# isoSPI_Interface.net
KiCad netlist of a schematic drawn in Altium Designer
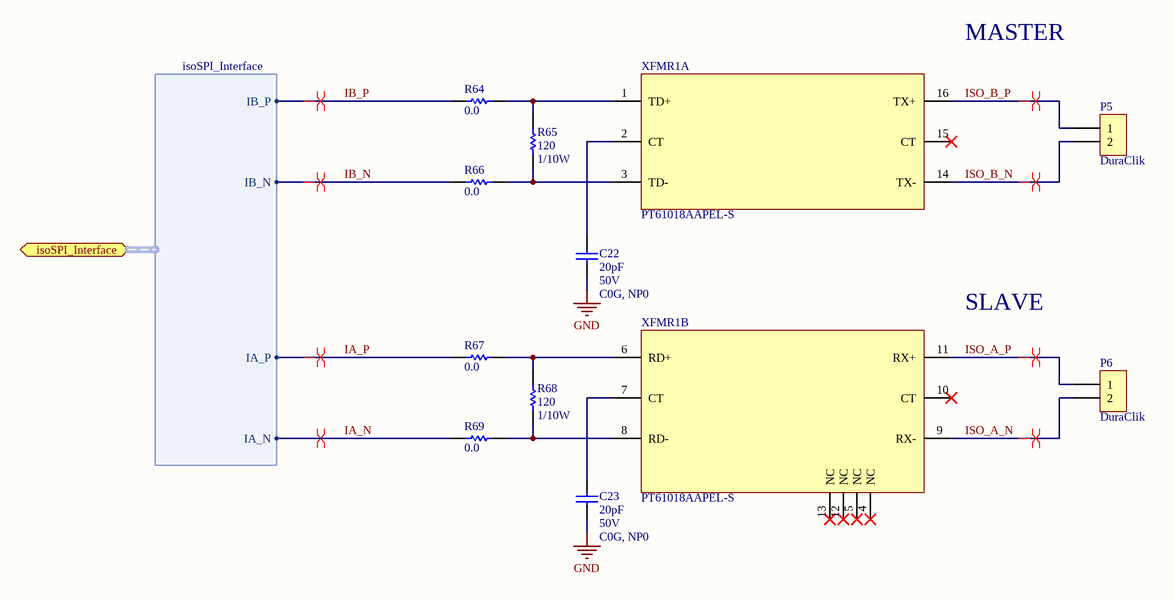
[diagram p0: isoSPI_Interface.SchDoc]

(export (version "E")
  (design (tool "Eeschema 10.0.6"))
  (components
    (comp (ref "C22")
      (value "CAP CER 20PF 50V ±5% C0G/NP0 0603")
      (footprint "CAP, 0603")
      (description "20pF ±5% 50V Ceramic Capacitor C0G, NP0 0603 (1608 Metric)")
      (fields
        (field (name "TOLERANCE") "±5%")
        (field (name "CAPACITANCE") "20pF")
        (field (name "VOLTAGE") "50V")
        (field (name "TEMPERATURE COEFFICIENT") "C0G, NP0")
      )
      (libsource (lib "Schematic Diagrams") (part "CAP CER 20PF 50V ±5% C0G/NP0 0603"))
    )
    (comp (ref "C23")
      (value "CAP CER 20PF 50V ±5% C0G/NP0 0603")
      (footprint "CAP, 0603")
      (description "20pF ±5% 50V Ceramic Capacitor C0G, NP0 0603 (1608 Metric)")
      (fields
        (field (name "TOLERANCE") "±5%")
        (field (name "CAPACITANCE") "20pF")
        (field (name "VOLTAGE") "50V")
        (field (name "TEMPERATURE COEFFICIENT") "C0G, NP0")
      )
      (libsource (lib "Schematic Diagrams") (part "CAP CER 20PF 50V ±5% C0G/NP0 0603"))
    )
    (comp (ref "P5")
      (value "CONN 2POS DURA-CLIK 0.079\"")
      (footprint "CONN, 2POS Dura-Click")
      (description "2 Positions Header, Shrouded Connector 0.079\" (2.00mm) Surface Mount, Right Angle Tin")
      (fields (field (name "SERIES") "DuraClik"))
      (libsource (lib "Schematic Diagrams") (part "CONN 2POS DURA-CLIK 0.079{dblquote}"))
    )
    (comp (ref "P6")
      (value "CONN 2POS DURA-CLIK 0.079\"")
      (footprint "CONN, 2POS Dura-Click")
      (description "2 Positions Header, Shrouded Connector 0.079\" (2.00mm) Surface Mount, Right Angle Tin")
      (fields (field (name "SERIES") "DuraClik"))
      (libsource (lib "Schematic Diagrams") (part "CONN 2POS DURA-CLIK 0.079{dblquote}"))
    )
    (comp (ref "R64")
      (value "RES 0.0 OHM 1/4W 0603")
      (footprint "RES, 0603")
      (description "RES SMD 0.0 OHM JUMPER 1/4W 0603")
      (fields (field (name "RESISTANCE") "0.0"))
      (libsource (lib "Schematic Diagrams") (part "RES 0.0 OHM 1/4W 0603"))
    )
    (comp (ref "R65")
      (value "RES 120 OHM 1% 1/10W 0603")
      (footprint "RES, 0603")
      (description "RES SMD 120 OHM 1% 1/10W 0603")
      (fields
        (field (name "TOLERANCE") "±1%")
        (field (name "RESISTANCE") "120")
        (field (name "POWER") "1/10W")
      )
      (libsource (lib "Schematic Diagrams") (part "RES 120 OHM 1% 1/10W 0603"))
    )
    (comp (ref "R66")
      (value "RES 0.0 OHM 1/4W 0603")
      (footprint "RES, 0603")
      (description "RES SMD 0.0 OHM JUMPER 1/4W 0603")
      (fields (field (name "RESISTANCE") "0.0"))
      (libsource (lib "Schematic Diagrams") (part "RES 0.0 OHM 1/4W 0603"))
    )
    (comp (ref "R67")
      (value "RES 0.0 OHM 1/4W 0603")
      (footprint "RES, 0603")
      (description "RES SMD 0.0 OHM JUMPER 1/4W 0603")
      (fields (field (name "RESISTANCE") "0.0"))
      (libsource (lib "Schematic Diagrams") (part "RES 0.0 OHM 1/4W 0603"))
    )
    (comp (ref "R68")
      (value "RES 120 OHM 1% 1/10W 0603")
      (footprint "RES, 0603")
      (description "RES SMD 120 OHM 1% 1/10W 0603")
      (fields
        (field (name "TOLERANCE") "±1%")
        (field (name "RESISTANCE") "120")
        (field (name "POWER") "1/10W")
      )
      (libsource (lib "Schematic Diagrams") (part "RES 120 OHM 1% 1/10W 0603"))
    )
    (comp (ref "R69")
      (value "RES 0.0 OHM 1/4W 0603")
      (footprint "RES, 0603")
      (description "RES SMD 0.0 OHM JUMPER 1/4W 0603")
      (fields (field (name "RESISTANCE") "0.0"))
      (libsource (lib "Schematic Diagrams") (part "RES 0.0 OHM 1/4W 0603"))
    )
    (comp (ref "XFMR1")
      (value "IC PULSE XFMR 1CT:1CT 350UH SMD")
      (footprint "IC, PULSE XFMR 1CT:1CT 350UH SMD")
      (description "PULSE XFMR 1CT:1CT 350UH SMD")
      (fields (field (name "MANUFACTURER") "Bourns Inc.") (field (name "MFG_PN") "PT61018AAPEL-S"))
      (libsource (lib "Schematic Diagrams") (part "IC PULSE XFMR 1CT{colon}1CT 350UH SMD"))
    )
  )
  (nets
    (net (code "2") (name "/IA_N") (class "Default")
      (node (ref "R69") (pin "1") (pinfunction "1_1") (pintype "passive"))
    )
    (net (code "3") (name "/IA_P") (class "Default")
      (node (ref "R67") (pin "1") (pinfunction "1_1") (pintype "passive"))
    )
    (net (code "4") (name "/IB_N") (class "Default")
      (node (ref "R66") (pin "1") (pinfunction "1_1") (pintype "passive"))
    )
    (net (code "5") (name "/IB_P") (class "Default")
      (node (ref "R64") (pin "1") (pinfunction "1_1") (pintype "passive"))
    )
    (net (code "6") (name "/ISO_A_N") (class "Default")
      (node (ref "P6") (pin "2") (pinfunction "2_2") (pintype "passive"))
      (node (ref "XFMR1") (pin "9") (pinfunction "RX-_9") (pintype "passive"))
    )
    (net (code "7") (name "/ISO_A_P") (class "Default")
      (node (ref "P6") (pin "1") (pinfunction "1_1") (pintype "passive"))
      (node (ref "XFMR1") (pin "11") (pinfunction "RX+_11") (pintype "passive"))
    )
    (net (code "8") (name "/ISO_B_N") (class "Default")
      (node (ref "P5") (pin "2") (pinfunction "2_2") (pintype "passive"))
      (node (ref "XFMR1") (pin "14") (pinfunction "TX-_14") (pintype "passive"))
    )
    (net (code "9") (name "/ISO_B_P") (class "Default")
      (node (ref "P5") (pin "1") (pinfunction "1_1") (pintype "passive"))
      (node (ref "XFMR1") (pin "16") (pinfunction "TX+_16") (pintype "passive"))
    )
    (net (code "11") (name "GND") (class "Default")
      (node (ref "C22") (pin "2") (pinfunction "2_2") (pintype "passive"))
      (node (ref "C23") (pin "2") (pinfunction "2_2") (pintype "passive"))
    )
    (net (code "12") (name "Net-(C22-Pad1)") (class "Default")
      (node (ref "C22") (pin "1") (pinfunction "1_1") (pintype "passive"))
      (node (ref "XFMR1") (pin "2") (pinfunction "CT_2") (pintype "passive"))
    )
    (net (code "13") (name "Net-(C23-Pad1)") (class "Default")
      (node (ref "C23") (pin "1") (pinfunction "1_1") (pintype "passive"))
      (node (ref "XFMR1") (pin "7") (pinfunction "CT_7") (pintype "passive"))
    )
    (net (code "14") (name "Net-(XFMR1A-TD+)") (class "Default")
      (node (ref "R64") (pin "2") (pinfunction "2_2") (pintype "passive"))
      (node (ref "R65") (pin "1") (pinfunction "1_1") (pintype "passive"))
      (node (ref "XFMR1") (pin "1") (pinfunction "TD+_1") (pintype "passive"))
    )
    (net (code "15") (name "Net-(XFMR1A-TD-)") (class "Default")
      (node (ref "R65") (pin "2") (pinfunction "2_2") (pintype "passive"))
      (node (ref "R66") (pin "2") (pinfunction "2_2") (pintype "passive"))
      (node (ref "XFMR1") (pin "3") (pinfunction "TD-_3") (pintype "passive"))
    )
    (net (code "16") (name "Net-(XFMR1B-RD+)") (class "Default")
      (node (ref "R67") (pin "2") (pinfunction "2_2") (pintype "passive"))
      (node (ref "R68") (pin "1") (pinfunction "1_1") (pintype "passive"))
      (node (ref "XFMR1") (pin "6") (pinfunction "RD+_6") (pintype "passive"))
    )
    (net (code "17") (name "Net-(XFMR1B-RD-)") (class "Default")
      (node (ref "R68") (pin "2") (pinfunction "2_2") (pintype "passive"))
      (node (ref "R69") (pin "2") (pinfunction "2_2") (pintype "passive"))
      (node (ref "XFMR1") (pin "8") (pinfunction "RD-_8") (pintype "passive"))
    )
    (net (code "18") (name "unconnected-(XFMR1A-CT-Pad15)") (class "Default")
      (node (ref "XFMR1") (pin "15") (pinfunction "CT_15") (pintype "passive+no_connect"))
    )
    (net (code "19") (name "unconnected-(XFMR1B-CT-Pad10)") (class "Default")
      (node (ref "XFMR1") (pin "10") (pinfunction "CT_10") (pintype "passive+no_connect"))
    )
    (net (code "20") (name "unconnected-(XFMR1B-NC-Pad4)") (class "Default")
      (node (ref "XFMR1") (pin "4") (pinfunction "NC_4") (pintype "passive+no_connect"))
    )
    (net (code "21") (name "unconnected-(XFMR1B-NC-Pad5)") (class "Default")
      (node (ref "XFMR1") (pin "5") (pinfunction "NC_5") (pintype "passive+no_connect"))
    )
    (net (code "22") (name "unconnected-(XFMR1B-NC-Pad12)") (class "Default")
      (node (ref "XFMR1") (pin "12") (pinfunction "NC_12") (pintype "passive+no_connect"))
    )
    (net (code "23") (name "unconnected-(XFMR1B-NC-Pad13)") (class "Default")
      (node (ref "XFMR1") (pin "13") (pinfunction "NC_13") (pintype "passive+no_connect"))
    )
  )
)
